# ProProject___2024-07-07.net
KiCad netlist of a schematic drawn in EasyEDA Pro
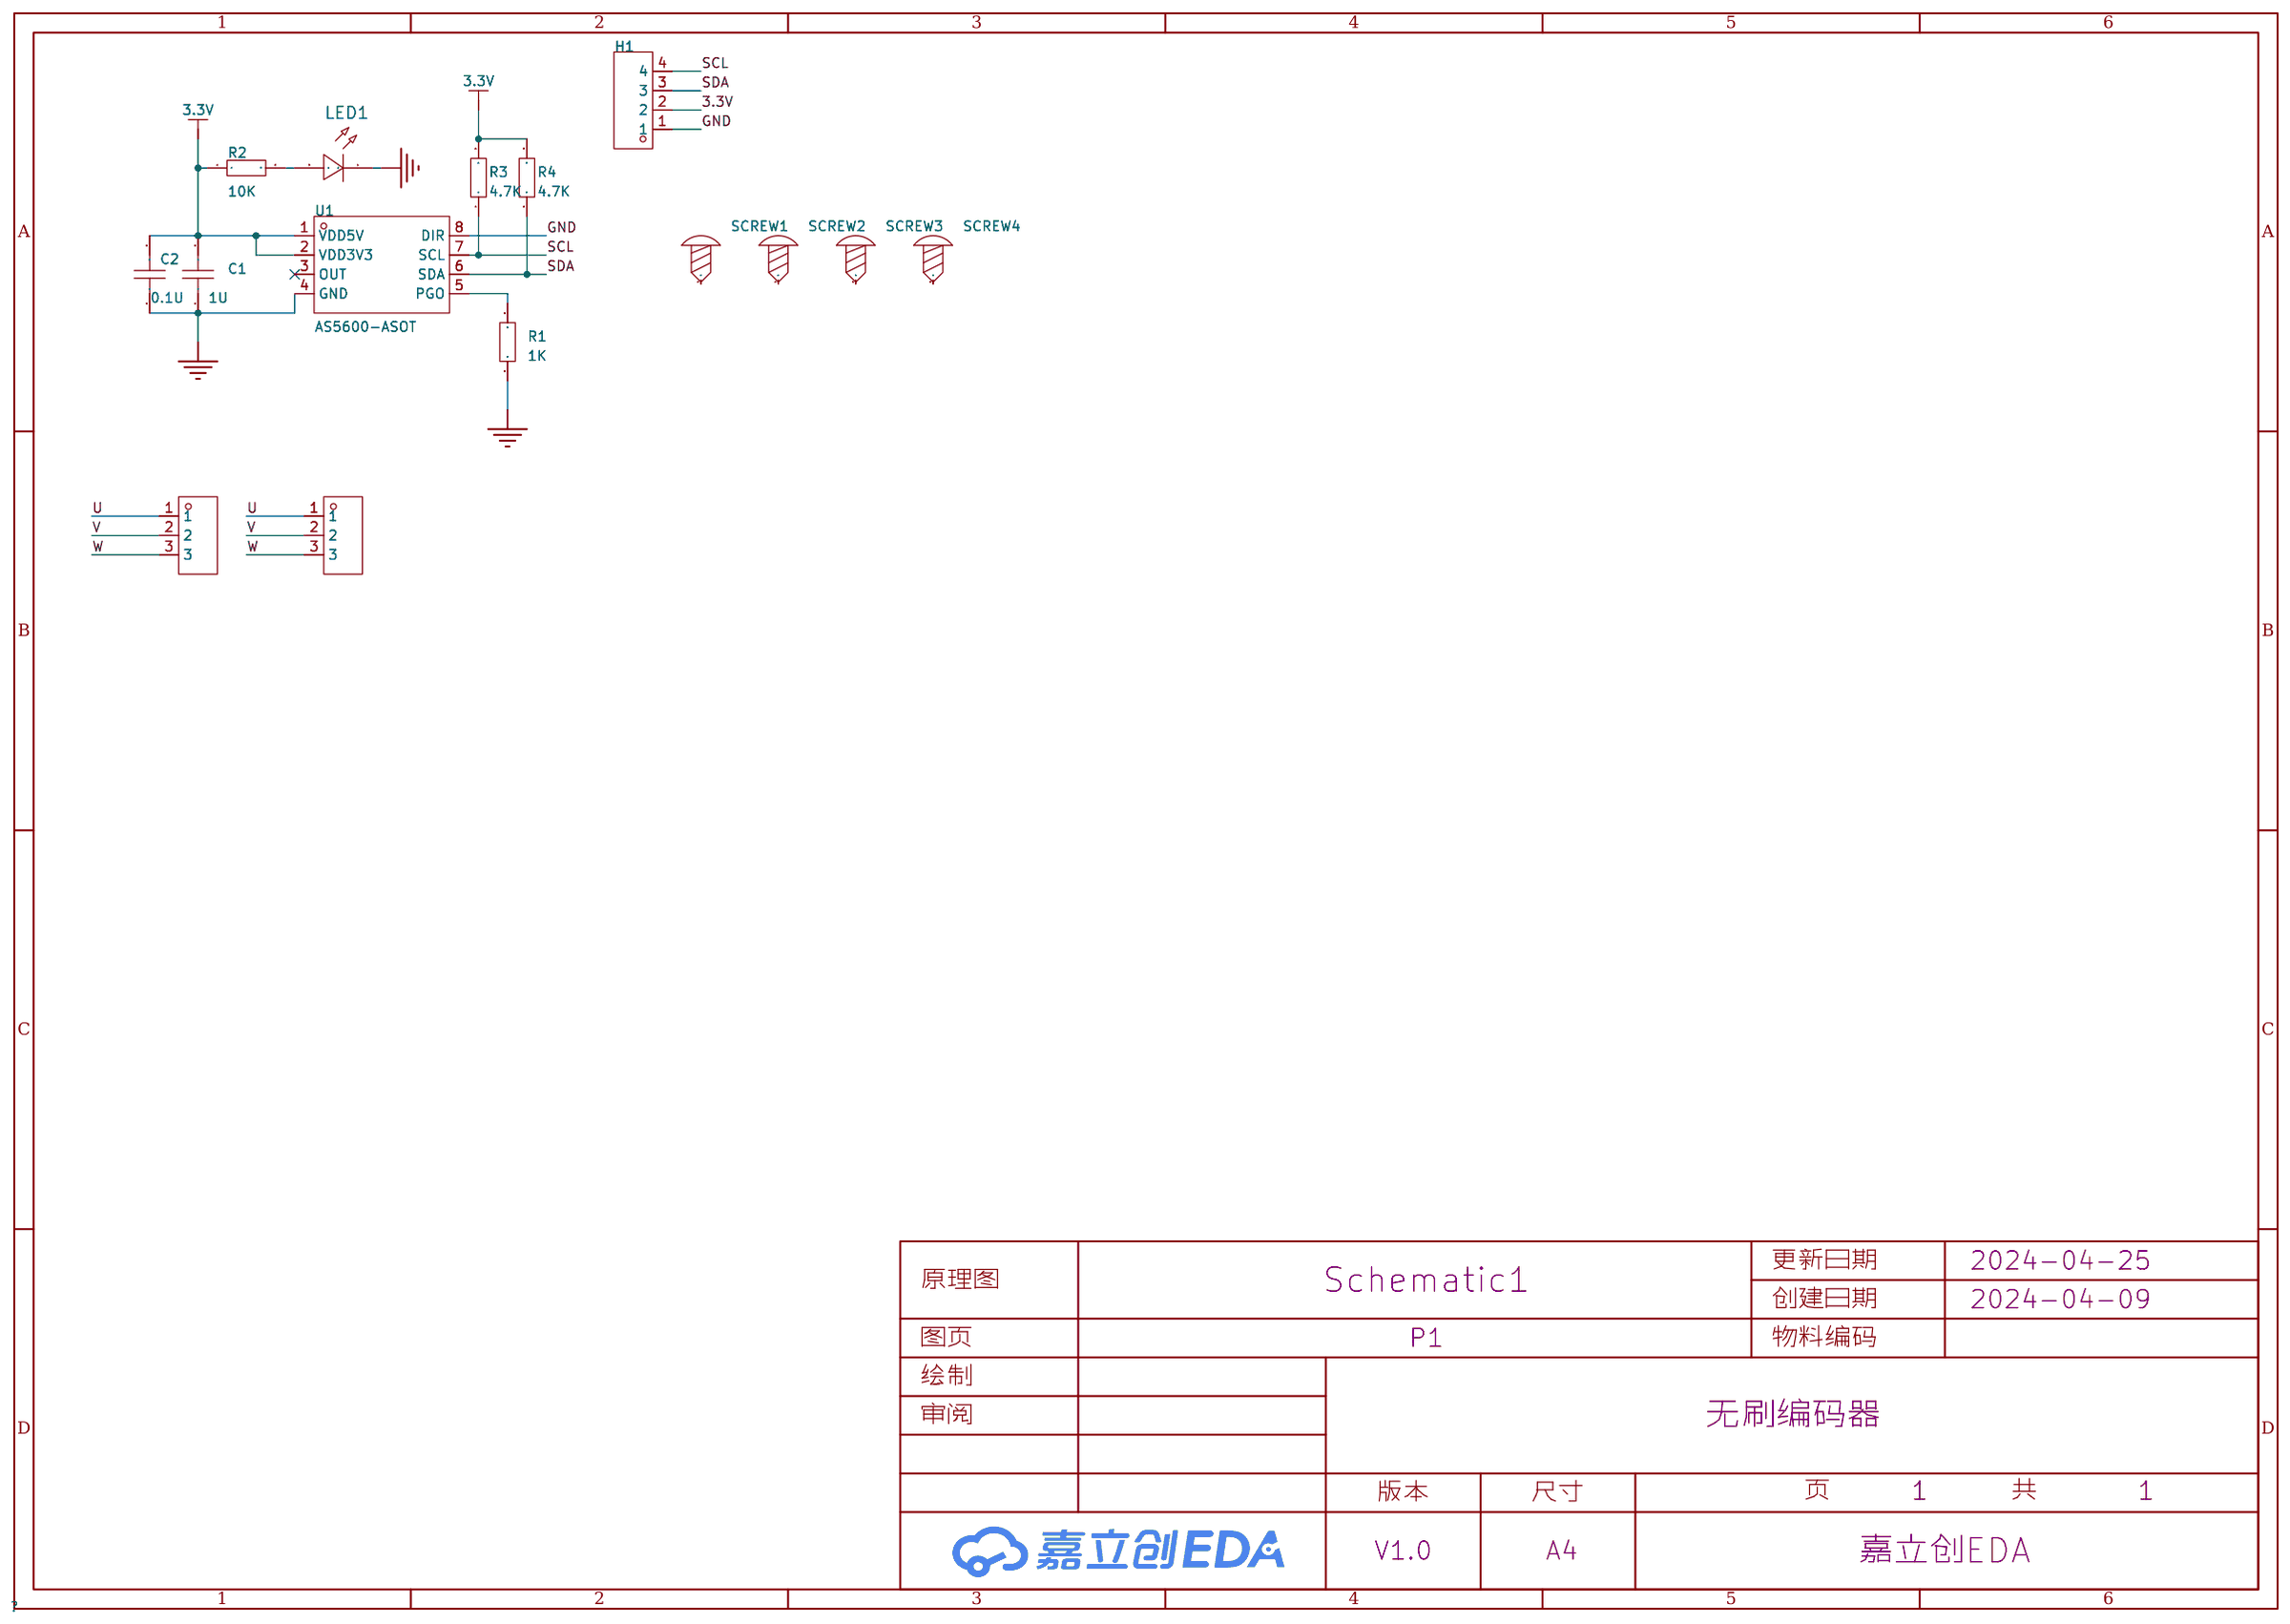
[diagram p0: schematic sheet]

(export (version "E")
  (design (tool "Eeschema 10.0.6"))
  (components
    (comp (ref "C1")
      (value "1U")
      (footprint "easyedapro:C0603")
      (libsource (lib "easyedapro") (part "CapAcitance"))
    )
    (comp (ref "C2")
      (value "0.1U")
      (footprint "easyedapro:C0603")
      (libsource (lib "easyedapro") (part "CapAcitance"))
    )
    (comp (ref "H1")
      (value "~")
      (footprint "easyedapro:HDR-TH_4P-P2.54-V-M")
      (libsource (lib "easyedapro") (part "PZ254V-11-04P"))
    )
    (comp (ref "LED1")
      (value "~")
      (footprint "easyedapro:LED_0603")
      (libsource (lib "easyedapro") (part "LED_R"))
    )
    (comp (ref "R1") (value "1K") (footprint "easyedapro:R0603") (libsource (lib "easyedapro") (part "电阻")))
    (comp (ref "R2") (value "10K") (footprint "easyedapro:R0603") (libsource (lib "easyedapro") (part "电阻")))
    (comp (ref "R3") (value "4.7K") (footprint "easyedapro:R0603") (libsource (lib "easyedapro") (part "电阻")))
    (comp (ref "R4") (value "4.7K") (footprint "easyedapro:R0603") (libsource (lib "easyedapro") (part "电阻")))
    (comp (ref "SCREW1")
      (value "~")
      (footprint "easyedapro:M3螺丝")
      (libsource (lib "easyedapro") (part "螺丝孔"))
    )
    (comp (ref "SCREW2")
      (value "~")
      (footprint "easyedapro:M3螺丝")
      (libsource (lib "easyedapro") (part "螺丝孔"))
    )
    (comp (ref "SCREW3")
      (value "~")
      (footprint "easyedapro:M3螺丝")
      (libsource (lib "easyedapro") (part "螺丝孔"))
    )
    (comp (ref "SCREW4")
      (value "~")
      (footprint "easyedapro:M3螺丝")
      (libsource (lib "easyedapro") (part "螺丝孔"))
    )
    (comp (ref "U1")
      (value "AS5600-ASOT")
      (footprint "easyedapro:SOIC-8_L5.0-W4.0-P1.27-LS6.0-BL")
      (description "旋转角度范围:0°~360°;")
      (fields (field (name "Manufacturer") "ams(艾迈斯半导体)"))
      (libsource (lib "easyedapro") (part "AS5600-ASOT"))
    )
    (comp (ref "U11")
      (value "KF301-5.0-3P")
      (footprint "easyedapro:CONN-TH_3P-P5.00_KF301-5.0-3P")
      (fields (field (name "Manufacturer") "KEFA(科发)"))
      (libsource (lib "easyedapro") (part "KF301-5.0-3P"))
    )
    (comp (ref "U12")
      (value "KF301-5.0-3P")
      (footprint "easyedapro:CONN-TH_3P-P5.00_KF301-5.0-3P")
      (fields (field (name "Manufacturer") "KEFA(科发)"))
      (libsource (lib "easyedapro") (part "KF301-5.0-3P"))
    )
  )
  (nets
    (net (code "1") (name "/SCL") (class "Default")
      (node (ref "H1") (pin "4") (pinfunction "4_4") (pintype "unspecified"))
      (node (ref "R3") (pin "1") (pinfunction "1_1") (pintype "input"))
      (node (ref "U1") (pin "7") (pinfunction "SCL_7") (pintype "input"))
    )
    (net (code "2") (name "/SDA") (class "Default")
      (node (ref "H1") (pin "3") (pinfunction "3_3") (pintype "unspecified"))
      (node (ref "R4") (pin "1") (pinfunction "1_1") (pintype "input"))
      (node (ref "U1") (pin "6") (pinfunction "SDA_6") (pintype "input"))
    )
    (net (code "3") (name "/U") (class "Default")
      (node (ref "U11") (pin "1") (pinfunction "1_1") (pintype "unspecified"))
      (node (ref "U12") (pin "1") (pinfunction "1_1") (pintype "unspecified"))
    )
    (net (code "4") (name "/V") (class "Default")
      (node (ref "U11") (pin "2") (pinfunction "2_2") (pintype "unspecified"))
      (node (ref "U12") (pin "2") (pinfunction "2_2") (pintype "unspecified"))
    )
    (net (code "5") (name "/W") (class "Default")
      (node (ref "U11") (pin "3") (pinfunction "3_3") (pintype "unspecified"))
      (node (ref "U12") (pin "3") (pinfunction "3_3") (pintype "unspecified"))
    )
    (net (code "6") (name "3.3V") (class "Default")
      (node (ref "C1") (pin "2") (pinfunction "2_2") (pintype "input"))
      (node (ref "C2") (pin "2") (pinfunction "2_2") (pintype "input"))
      (node (ref "H1") (pin "2") (pinfunction "2_2") (pintype "unspecified"))
      (node (ref "R2") (pin "1") (pinfunction "1_1") (pintype "input"))
      (node (ref "R3") (pin "2") (pinfunction "2_2") (pintype "input"))
      (node (ref "R4") (pin "2") (pinfunction "2_2") (pintype "input"))
      (node (ref "U1") (pin "1") (pinfunction "VDD5V_1") (pintype "input"))
      (node (ref "U1") (pin "2") (pinfunction "VDD3V3_2") (pintype "input"))
    )
    (net (code "7") (name "GND") (class "Default")
      (node (ref "C1") (pin "1") (pinfunction "1_1") (pintype "input"))
      (node (ref "C2") (pin "1") (pinfunction "1_1") (pintype "input"))
      (node (ref "H1") (pin "1") (pinfunction "1_1") (pintype "unspecified"))
      (node (ref "LED1") (pin "1") (pinfunction "C_1") (pintype "input"))
      (node (ref "R1") (pin "1") (pinfunction "1_1") (pintype "input"))
      (node (ref "U1") (pin "4") (pinfunction "GND_4") (pintype "input"))
      (node (ref "U1") (pin "8") (pinfunction "DIR_8") (pintype "input"))
    )
    (net (code "8") (name "Net-(LED1-A)") (class "Default")
      (node (ref "LED1") (pin "2") (pinfunction "A_2") (pintype "input"))
      (node (ref "R2") (pin "2") (pinfunction "2_2") (pintype "input"))
    )
    (net (code "9") (name "Net-(U1-PGO)") (class "Default")
      (node (ref "R1") (pin "2") (pinfunction "2_2") (pintype "input"))
      (node (ref "U1") (pin "5") (pinfunction "PGO_5") (pintype "input"))
    )
    (net (code "10") (name "unconnected-(SCREW1-Pad1)") (class "Default")
      (node (ref "SCREW1") (pin "1") (pinfunction "1_1") (pintype "input"))
    )
    (net (code "11") (name "unconnected-(SCREW2-Pad1)") (class "Default")
      (node (ref "SCREW2") (pin "1") (pinfunction "1_1") (pintype "input"))
    )
    (net (code "12") (name "unconnected-(SCREW3-Pad1)") (class "Default")
      (node (ref "SCREW3") (pin "1") (pinfunction "1_1") (pintype "input"))
    )
    (net (code "13") (name "unconnected-(SCREW4-Pad1)") (class "Default")
      (node (ref "SCREW4") (pin "1") (pinfunction "1_1") (pintype "input"))
    )
    (net (code "14") (name "unconnected-(U1-OUT-Pad3)") (class "Default")
      (node (ref "U1") (pin "3") (pinfunction "OUT_3") (pintype "input+no_connect"))
    )
  )
)
